# 32nbIoT-1_2.net
KiCad netlist of a schematic drawn in EAGLE
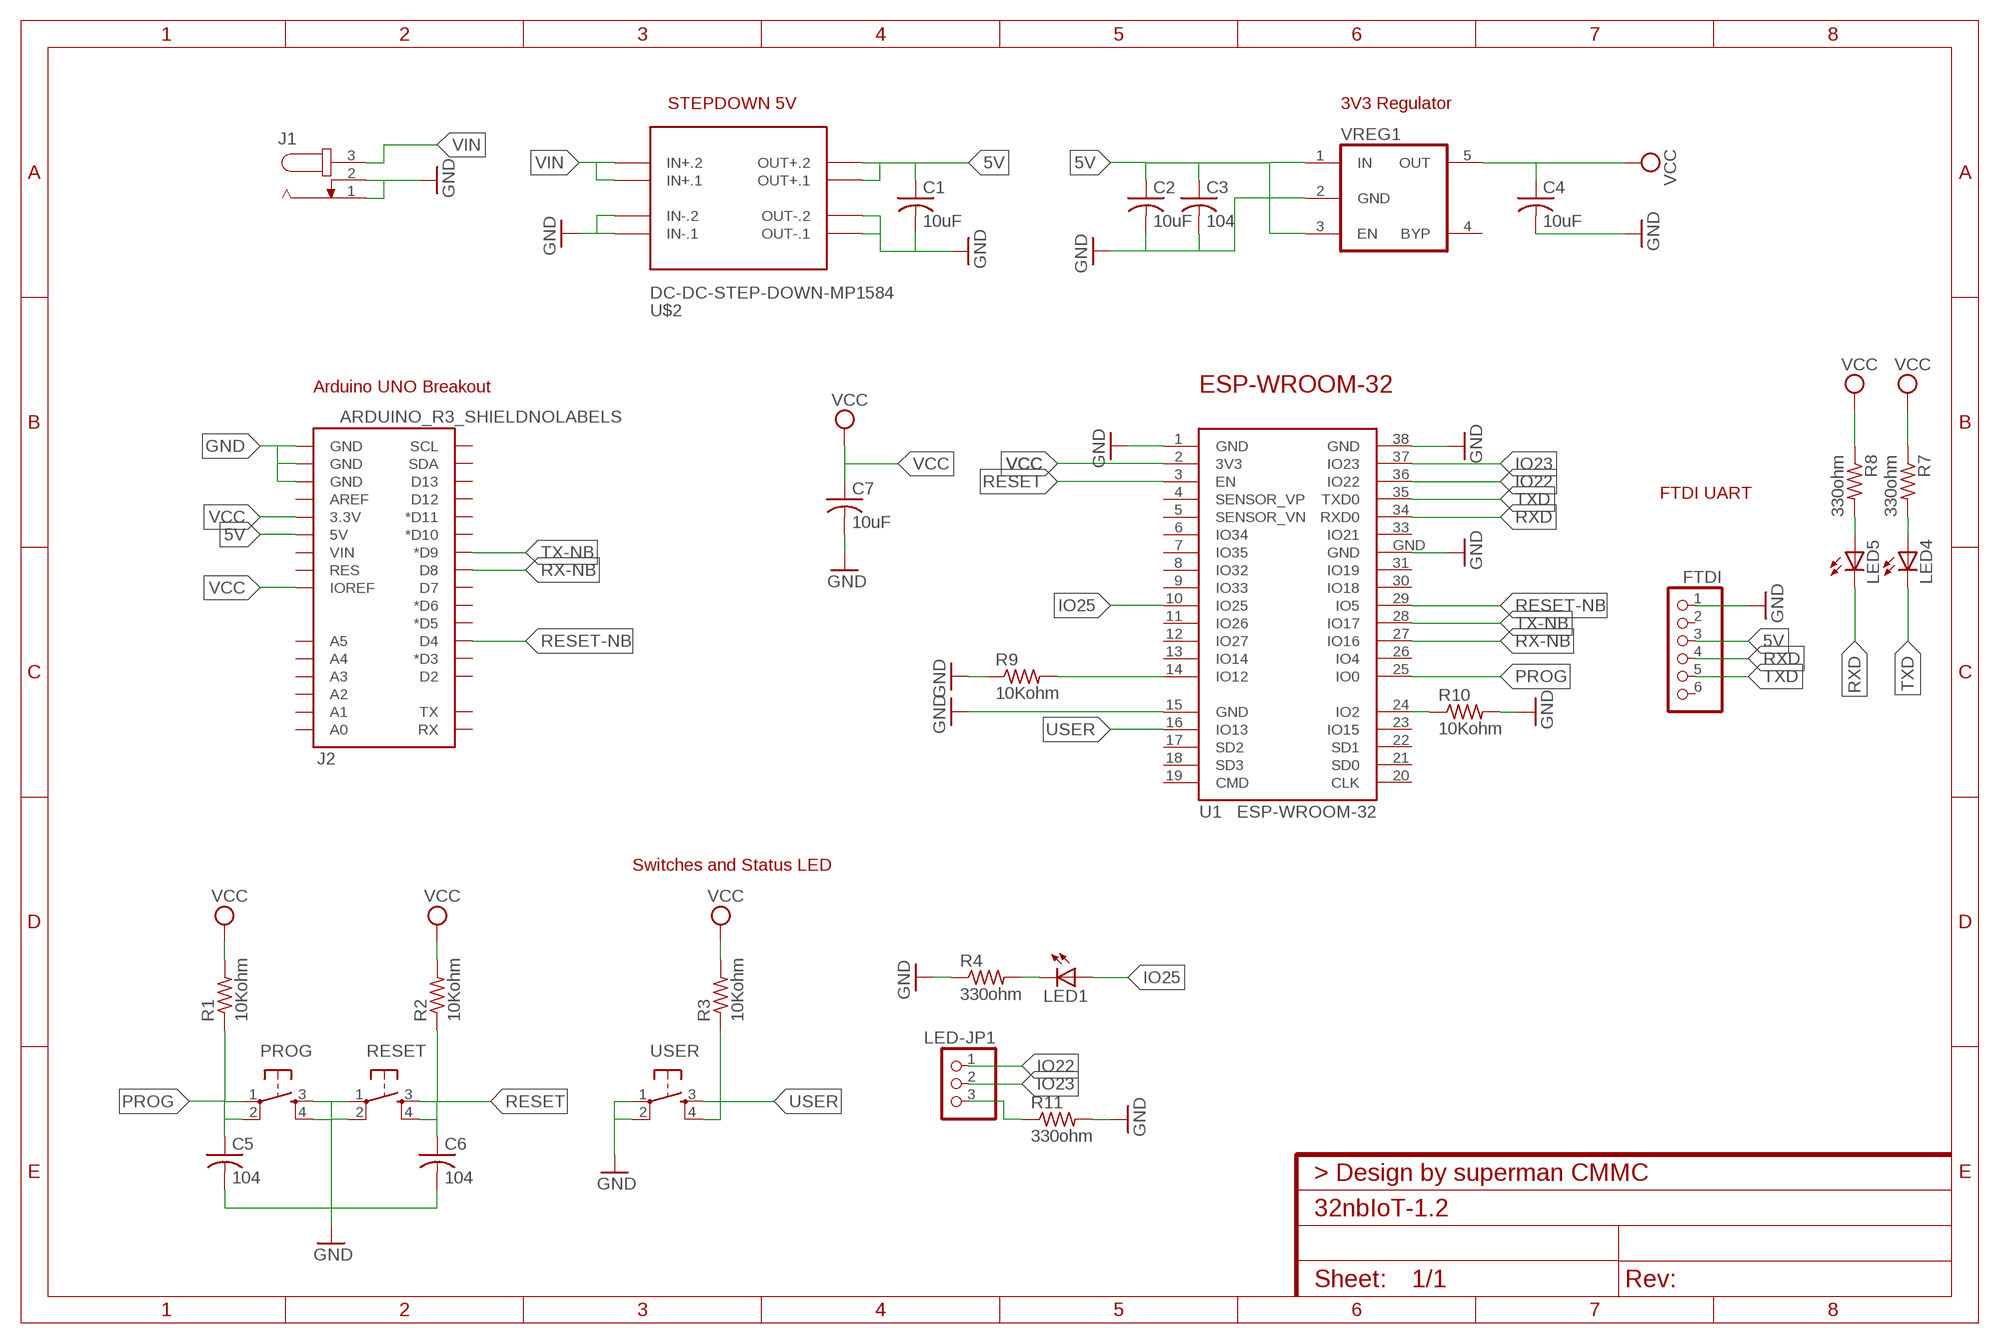
[diagram p0: schematic, sheet 1]

(export (version "E")
  (design (tool "Eeschema 10.0.6"))
  (components
    (comp (ref "C1")
      (value "10uF")
      (footprint "eagle-import:C0805")
      (libsource (lib "eagle-import") (part "C-USC0805"))
    )
    (comp (ref "C2")
      (value "10uF")
      (footprint "eagle-import:C0805")
      (libsource (lib "eagle-import") (part "C-USC0805"))
    )
    (comp (ref "C3")
      (value "104")
      (footprint "eagle-import:C0805")
      (libsource (lib "eagle-import") (part "C-USC0805"))
    )
    (comp (ref "C4")
      (value "10uF")
      (footprint "eagle-import:C0805")
      (libsource (lib "eagle-import") (part "C-USC0805"))
    )
    (comp (ref "C5")
      (value "104")
      (footprint "eagle-import:C0805")
      (libsource (lib "eagle-import") (part "C-USC0805"))
    )
    (comp (ref "C6")
      (value "104")
      (footprint "eagle-import:C0805")
      (libsource (lib "eagle-import") (part "C-USC0805"))
    )
    (comp (ref "C7")
      (value "10uF")
      (footprint "eagle-import:C0805")
      (libsource (lib "eagle-import") (part "C-USC0805"))
    )
    (comp (ref "FTDI")
      (value "PINHD-1X6")
      (footprint "eagle-import:1X06")
      (libsource (lib "eagle-import") (part "PINHD-1X6"))
    )
    (comp (ref "J1")
      (value "JACK-PLUG1")
      (footprint "eagle-import:SPC4078")
      (libsource (lib "eagle-import") (part "JACK-PLUG1"))
    )
    (comp (ref "J2")
      (value "ARDUINO_R3_SHIELDNOLABELS")
      (footprint "eagle-import:UNO_R3_SHIELD_NOLABELS")
      (libsource (lib "eagle-import") (part "ARDUINO_R3_SHIELDNOLABELS"))
    )
    (comp (ref "LED-JP1")
      (value "PINHD-1X3/90")
      (footprint "eagle-import:1X03_90")
      (libsource (lib "eagle-import") (part "PINHD-1X3/90"))
    )
    (comp (ref "LED1")
      (value "LEDCHIPLED_0805")
      (footprint "eagle-import:CHIPLED_0805")
      (libsource (lib "eagle-import") (part "LEDCHIPLED_0805"))
    )
    (comp (ref "LED4")
      (value "LEDCHIPLED_0805")
      (footprint "eagle-import:CHIPLED_0805")
      (libsource (lib "eagle-import") (part "LEDCHIPLED_0805"))
    )
    (comp (ref "LED5")
      (value "LEDCHIPLED_0805")
      (footprint "eagle-import:CHIPLED_0805")
      (libsource (lib "eagle-import") (part "LEDCHIPLED_0805"))
    )
    (comp (ref "PROG")
      (value "TAC_SWITCHPTH")
      (footprint "eagle-import:TACTILE-PTH")
      (libsource (lib "eagle-import") (part "TAC_SWITCHPTH"))
    )
    (comp (ref "R1")
      (value "10Kohm")
      (footprint "eagle-import:R0805W")
      (libsource (lib "eagle-import") (part "R-US_R0805W"))
    )
    (comp (ref "R2")
      (value "10Kohm")
      (footprint "eagle-import:R0805W")
      (libsource (lib "eagle-import") (part "R-US_R0805W"))
    )
    (comp (ref "R3")
      (value "10Kohm")
      (footprint "eagle-import:R0805W")
      (libsource (lib "eagle-import") (part "R-US_R0805W"))
    )
    (comp (ref "R4")
      (value "330ohm")
      (footprint "eagle-import:R0805W")
      (libsource (lib "eagle-import") (part "R-US_R0805W"))
    )
    (comp (ref "R7")
      (value "330ohm")
      (footprint "eagle-import:R0805W")
      (libsource (lib "eagle-import") (part "R-US_R0805W"))
    )
    (comp (ref "R8")
      (value "330ohm")
      (footprint "eagle-import:R0805W")
      (libsource (lib "eagle-import") (part "R-US_R0805W"))
    )
    (comp (ref "R9")
      (value "10Kohm")
      (footprint "eagle-import:R0805W")
      (libsource (lib "eagle-import") (part "R-US_R0805W"))
    )
    (comp (ref "R10")
      (value "10Kohm")
      (footprint "eagle-import:R0805W")
      (libsource (lib "eagle-import") (part "R-US_R0805W"))
    )
    (comp (ref "R11")
      (value "330ohm")
      (footprint "eagle-import:R0805W")
      (libsource (lib "eagle-import") (part "R-US_R0805W"))
    )
    (comp (ref "RESET")
      (value "TAC_SWITCHPTH")
      (footprint "eagle-import:TACTILE-PTH")
      (libsource (lib "eagle-import") (part "TAC_SWITCHPTH"))
    )
    (comp (ref "U$2")
      (value "DC-DC-STEP-DOWN-MP1584")
      (footprint "eagle-import:DC-DC-STEP-DOWN-MP1584")
      (libsource (lib "eagle-import") (part "DC-DC-STEP-DOWN-MP1584"))
    )
    (comp (ref "U1")
      (value "ESP-WROOM-32")
      (footprint "eagle-import:ESP-WROOM-32")
      (libsource (lib "eagle-import") (part "ESP-WROOM-32"))
    )
    (comp (ref "USER")
      (value "TAC_SWITCHPTH")
      (footprint "eagle-import:TACTILE-PTH")
      (libsource (lib "eagle-import") (part "TAC_SWITCHPTH"))
    )
    (comp (ref "VREG1")
      (value "VREG_5PINS-SOT-23-5")
      (footprint "eagle-import:SOT-23-5")
      (libsource (lib "eagle-import") (part "VREG_5PINS-SOT-23-5"))
    )
  )
  (nets
    (net (code "1") (name "5V") (class "Default")
      (node (ref "C1") (pin "1") (pinfunction "1_1") (pintype "passive"))
      (node (ref "C2") (pin "1") (pinfunction "1_1") (pintype "passive"))
      (node (ref "C3") (pin "1") (pinfunction "1_1") (pintype "passive"))
      (node (ref "FTDI") (pin "3") (pinfunction "3_3") (pintype "passive"))
      (node (ref "J2") (pin "5V") (pinfunction "5V_5V") (pintype "bidirectional"))
      (node (ref "U$2") (pin "OUT+.1") (pinfunction "OUT+.1_OUT+.1") (pintype "bidirectional"))
      (node (ref "U$2") (pin "OUT+.2") (pinfunction "OUT+.2_OUT+.2") (pintype "bidirectional"))
      (node (ref "VREG1") (pin "1") (pinfunction "IN_1") (pintype "bidirectional"))
      (node (ref "VREG1") (pin "3") (pinfunction "EN_3") (pintype "bidirectional"))
    )
    (net (code "2") (name "GND") (class "Default")
      (node (ref "C1") (pin "2") (pinfunction "2_2") (pintype "passive"))
      (node (ref "C2") (pin "2") (pinfunction "2_2") (pintype "passive"))
      (node (ref "C3") (pin "2") (pinfunction "2_2") (pintype "passive"))
      (node (ref "C4") (pin "2") (pinfunction "2_2") (pintype "passive"))
      (node (ref "C5") (pin "2") (pinfunction "2_2") (pintype "passive"))
      (node (ref "C6") (pin "2") (pinfunction "2_2") (pintype "passive"))
      (node (ref "C7") (pin "2") (pinfunction "2_2") (pintype "passive"))
      (node (ref "FTDI") (pin "1") (pinfunction "1_1") (pintype "passive"))
      (node (ref "J1") (pin "1") (pinfunction "1_1") (pintype "passive"))
      (node (ref "J1") (pin "2") (pinfunction "2_2") (pintype "passive"))
      (node (ref "J2") (pin "GND@0") (pinfunction "GND_GND@0") (pintype "bidirectional"))
      (node (ref "J2") (pin "GND@1") (pinfunction "GND_GND@1") (pintype "bidirectional"))
      (node (ref "J2") (pin "GND@2") (pinfunction "GND_GND@2") (pintype "bidirectional"))
      (node (ref "PROG") (pin "3") (pinfunction "3_3") (pintype "passive"))
      (node (ref "PROG") (pin "4") (pinfunction "4_4") (pintype "passive"))
      (node (ref "R10") (pin "2") (pinfunction "2_2") (pintype "passive"))
      (node (ref "R11") (pin "2") (pinfunction "2_2") (pintype "passive"))
      (node (ref "R4") (pin "1") (pinfunction "1_1") (pintype "passive"))
      (node (ref "R9") (pin "1") (pinfunction "1_1") (pintype "passive"))
      (node (ref "RESET") (pin "1") (pinfunction "1_1") (pintype "passive"))
      (node (ref "RESET") (pin "2") (pinfunction "2_2") (pintype "passive"))
      (node (ref "U$2") (pin "IN-.1") (pinfunction "IN-.1_IN-.1") (pintype "bidirectional"))
      (node (ref "U$2") (pin "IN-.2") (pinfunction "IN-.2_IN-.2") (pintype "bidirectional"))
      (node (ref "U$2") (pin "OUT-.1") (pinfunction "OUT-.1_OUT-.1") (pintype "bidirectional"))
      (node (ref "U$2") (pin "OUT-.2") (pinfunction "OUT-.2_OUT-.2") (pintype "bidirectional"))
      (node (ref "U1") (pin "1") (pinfunction "GND_1") (pintype "power_in"))
      (node (ref "U1") (pin "15") (pinfunction "GND_15") (pintype "power_in"))
      (node (ref "U1") (pin "38") (pinfunction "GND_38") (pintype "power_in"))
      (node (ref "U1") (pin "GND") (pinfunction "GND_GND") (pintype "power_in"))
      (node (ref "USER") (pin "1") (pinfunction "1_1") (pintype "passive"))
      (node (ref "USER") (pin "2") (pinfunction "2_2") (pintype "passive"))
      (node (ref "VREG1") (pin "2") (pinfunction "GND_2") (pintype "bidirectional"))
    )
    (net (code "3") (name "IO22") (class "Default")
      (node (ref "LED-JP1") (pin "1") (pinfunction "1_1") (pintype "passive"))
      (node (ref "U1") (pin "36") (pinfunction "IO22_36") (pintype "bidirectional"))
    )
    (net (code "4") (name "IO23") (class "Default")
      (node (ref "LED-JP1") (pin "2") (pinfunction "2_2") (pintype "passive"))
      (node (ref "U1") (pin "37") (pinfunction "IO23_37") (pintype "bidirectional"))
    )
    (net (code "5") (name "IO25") (class "Default")
      (node (ref "LED1") (pin "A") (pinfunction "A_A") (pintype "passive"))
      (node (ref "U1") (pin "10") (pinfunction "IO25_10") (pintype "bidirectional"))
    )
    (net (code "6") (name "Net-(LED-JP1-Pad3)") (class "Default")
      (node (ref "LED-JP1") (pin "3") (pinfunction "3_3") (pintype "passive"))
      (node (ref "R11") (pin "1") (pinfunction "1_1") (pintype "passive"))
    )
    (net (code "7") (name "Net-(LED1-PadC)") (class "Default")
      (node (ref "LED1") (pin "C") (pinfunction "C_C") (pintype "passive"))
      (node (ref "R4") (pin "2") (pinfunction "2_2") (pintype "passive"))
    )
    (net (code "8") (name "Net-(LED4-PadA)") (class "Default")
      (node (ref "LED4") (pin "A") (pinfunction "A_A") (pintype "passive"))
      (node (ref "R7") (pin "2") (pinfunction "2_2") (pintype "passive"))
    )
    (net (code "9") (name "Net-(LED5-PadA)") (class "Default")
      (node (ref "LED5") (pin "A") (pinfunction "A_A") (pintype "passive"))
      (node (ref "R8") (pin "2") (pinfunction "2_2") (pintype "passive"))
    )
    (net (code "10") (name "Net-(U1-IO2)") (class "Default")
      (node (ref "R10") (pin "1") (pinfunction "1_1") (pintype "passive"))
      (node (ref "U1") (pin "24") (pinfunction "IO2_24") (pintype "bidirectional"))
    )
    (net (code "11") (name "Net-(U1-IO12)") (class "Default")
      (node (ref "R9") (pin "2") (pinfunction "2_2") (pintype "passive"))
      (node (ref "U1") (pin "14") (pinfunction "IO12_14") (pintype "bidirectional"))
    )
    (net (code "12") (name "PROG") (class "Default")
      (node (ref "C5") (pin "1") (pinfunction "1_1") (pintype "passive"))
      (node (ref "PROG") (pin "1") (pinfunction "1_1") (pintype "passive"))
      (node (ref "PROG") (pin "2") (pinfunction "2_2") (pintype "passive"))
      (node (ref "R1") (pin "1") (pinfunction "1_1") (pintype "passive"))
      (node (ref "U1") (pin "25") (pinfunction "IO0_25") (pintype "bidirectional"))
    )
    (net (code "13") (name "RESET") (class "Default")
      (node (ref "C6") (pin "1") (pinfunction "1_1") (pintype "passive"))
      (node (ref "R2") (pin "1") (pinfunction "1_1") (pintype "passive"))
      (node (ref "RESET") (pin "3") (pinfunction "3_3") (pintype "passive"))
      (node (ref "RESET") (pin "4") (pinfunction "4_4") (pintype "passive"))
      (node (ref "U1") (pin "3") (pinfunction "EN_3") (pintype "input"))
    )
    (net (code "14") (name "RESET-NB") (class "Default")
      (node (ref "J2") (pin "D4") (pinfunction "D4_D4") (pintype "bidirectional"))
      (node (ref "U1") (pin "29") (pinfunction "IO5_29") (pintype "bidirectional"))
    )
    (net (code "15") (name "RX-NB") (class "Default")
      (node (ref "J2") (pin "D8") (pinfunction "D8_D8") (pintype "bidirectional"))
      (node (ref "U1") (pin "27") (pinfunction "IO16_27") (pintype "bidirectional"))
    )
    (net (code "16") (name "RXD") (class "Default")
      (node (ref "FTDI") (pin "4") (pinfunction "4_4") (pintype "passive"))
      (node (ref "LED5") (pin "C") (pinfunction "C_C") (pintype "passive"))
      (node (ref "U1") (pin "34") (pinfunction "RXD0_34") (pintype "bidirectional"))
    )
    (net (code "17") (name "TX-NB") (class "Default")
      (node (ref "J2") (pin "D9") (pinfunction "*D9_D9") (pintype "bidirectional"))
      (node (ref "U1") (pin "28") (pinfunction "IO17_28") (pintype "bidirectional"))
    )
    (net (code "18") (name "TXD") (class "Default")
      (node (ref "FTDI") (pin "5") (pinfunction "5_5") (pintype "passive"))
      (node (ref "LED4") (pin "C") (pinfunction "C_C") (pintype "passive"))
      (node (ref "U1") (pin "35") (pinfunction "TXD0_35") (pintype "bidirectional"))
    )
    (net (code "19") (name "USER") (class "Default")
      (node (ref "R3") (pin "1") (pinfunction "1_1") (pintype "passive"))
      (node (ref "U1") (pin "16") (pinfunction "IO13_16") (pintype "bidirectional"))
      (node (ref "USER") (pin "3") (pinfunction "3_3") (pintype "passive"))
      (node (ref "USER") (pin "4") (pinfunction "4_4") (pintype "passive"))
    )
    (net (code "20") (name "VCC") (class "Default")
      (node (ref "C4") (pin "1") (pinfunction "1_1") (pintype "passive"))
      (node (ref "C7") (pin "1") (pinfunction "1_1") (pintype "passive"))
      (node (ref "J2") (pin "3.3V") (pinfunction "3.3V_3.3V") (pintype "bidirectional"))
      (node (ref "J2") (pin "IOREF") (pinfunction "IOREF_IOREF") (pintype "bidirectional"))
      (node (ref "R1") (pin "2") (pinfunction "2_2") (pintype "passive"))
      (node (ref "R2") (pin "2") (pinfunction "2_2") (pintype "passive"))
      (node (ref "R3") (pin "2") (pinfunction "2_2") (pintype "passive"))
      (node (ref "R7") (pin "1") (pinfunction "1_1") (pintype "passive"))
      (node (ref "R8") (pin "1") (pinfunction "1_1") (pintype "passive"))
      (node (ref "U1") (pin "2") (pinfunction "3V3_2") (pintype "power_in"))
      (node (ref "VREG1") (pin "5") (pinfunction "OUT_5") (pintype "bidirectional"))
    )
    (net (code "21") (name "VIN") (class "Default")
      (node (ref "J1") (pin "3") (pinfunction "3_3") (pintype "passive"))
      (node (ref "U$2") (pin "IN+.1") (pinfunction "IN+.1_IN+.1") (pintype "bidirectional"))
      (node (ref "U$2") (pin "IN+.2") (pinfunction "IN+.2_IN+.2") (pintype "bidirectional"))
    )
    (net (code "22") (name "unconnected-(FTDI-Pad2)") (class "Default")
      (node (ref "FTDI") (pin "2") (pinfunction "2_2") (pintype "passive"))
    )
    (net (code "23") (name "unconnected-(FTDI-Pad6)") (class "Default")
      (node (ref "FTDI") (pin "6") (pinfunction "6_6") (pintype "passive"))
    )
    (net (code "24") (name "unconnected-(J2-*D3-PadD3)") (class "Default")
      (node (ref "J2") (pin "D3") (pinfunction "*D3_D3") (pintype "bidirectional"))
    )
    (net (code "25") (name "unconnected-(J2-*D5-PadD5)") (class "Default")
      (node (ref "J2") (pin "D5") (pinfunction "*D5_D5") (pintype "bidirectional"))
    )
    (net (code "26") (name "unconnected-(J2-*D6-PadD6)") (class "Default")
      (node (ref "J2") (pin "D6") (pinfunction "*D6_D6") (pintype "bidirectional"))
    )
    (net (code "27") (name "unconnected-(J2-*D10-PadD10)") (class "Default")
      (node (ref "J2") (pin "D10") (pinfunction "*D10_D10") (pintype "bidirectional"))
    )
    (net (code "28") (name "unconnected-(J2-*D11-PadD11)") (class "Default")
      (node (ref "J2") (pin "D11") (pinfunction "*D11_D11") (pintype "bidirectional"))
    )
    (net (code "29") (name "unconnected-(J2-PadA0)") (class "Default")
      (node (ref "J2") (pin "A0") (pinfunction "A0_A0") (pintype "bidirectional"))
    )
    (net (code "30") (name "unconnected-(J2-PadA1)") (class "Default")
      (node (ref "J2") (pin "A1") (pinfunction "A1_A1") (pintype "bidirectional"))
    )
    (net (code "31") (name "unconnected-(J2-PadA2)") (class "Default")
      (node (ref "J2") (pin "A2") (pinfunction "A2_A2") (pintype "bidirectional"))
    )
    (net (code "32") (name "unconnected-(J2-PadA3)") (class "Default")
      (node (ref "J2") (pin "A3") (pinfunction "A3_A3") (pintype "bidirectional"))
    )
    (net (code "33") (name "unconnected-(J2-PadA4)") (class "Default")
      (node (ref "J2") (pin "A4") (pinfunction "A4_A4") (pintype "bidirectional"))
    )
    (net (code "34") (name "unconnected-(J2-PadA5)") (class "Default")
      (node (ref "J2") (pin "A5") (pinfunction "A5_A5") (pintype "bidirectional"))
    )
    (net (code "35") (name "unconnected-(J2-PadAREF)") (class "Default")
      (node (ref "J2") (pin "AREF") (pinfunction "AREF_AREF") (pintype "bidirectional"))
    )
    (net (code "36") (name "unconnected-(J2-PadD2)") (class "Default")
      (node (ref "J2") (pin "D2") (pinfunction "D2_D2") (pintype "bidirectional"))
    )
    (net (code "37") (name "unconnected-(J2-PadD7)") (class "Default")
      (node (ref "J2") (pin "D7") (pinfunction "D7_D7") (pintype "bidirectional"))
    )
    (net (code "38") (name "unconnected-(J2-PadD12)") (class "Default")
      (node (ref "J2") (pin "D12") (pinfunction "D12_D12") (pintype "bidirectional"))
    )
    (net (code "39") (name "unconnected-(J2-PadD13)") (class "Default")
      (node (ref "J2") (pin "D13") (pinfunction "D13_D13") (pintype "bidirectional"))
    )
    (net (code "40") (name "unconnected-(J2-PadRES)") (class "Default")
      (node (ref "J2") (pin "RES") (pinfunction "RES_RES") (pintype "bidirectional"))
    )
    (net (code "41") (name "unconnected-(J2-PadRX)") (class "Default")
      (node (ref "J2") (pin "RX") (pinfunction "RX_RX") (pintype "bidirectional"))
    )
    (net (code "42") (name "unconnected-(J2-PadSCL)") (class "Default")
      (node (ref "J2") (pin "SCL") (pinfunction "SCL_SCL") (pintype "bidirectional"))
    )
    (net (code "43") (name "unconnected-(J2-PadSDA)") (class "Default")
      (node (ref "J2") (pin "SDA") (pinfunction "SDA_SDA") (pintype "bidirectional"))
    )
    (net (code "44") (name "unconnected-(J2-PadTX)") (class "Default")
      (node (ref "J2") (pin "TX") (pinfunction "TX_TX") (pintype "bidirectional"))
    )
    (net (code "45") (name "unconnected-(J2-PadVIN)") (class "Default")
      (node (ref "J2") (pin "VIN") (pinfunction "VIN_VIN") (pintype "bidirectional"))
    )
    (net (code "46") (name "unconnected-(U1-CLK-Pad20)") (class "Default")
      (node (ref "U1") (pin "20") (pinfunction "CLK_20") (pintype "bidirectional"))
    )
    (net (code "47") (name "unconnected-(U1-CMD-Pad19)") (class "Default")
      (node (ref "U1") (pin "19") (pinfunction "CMD_19") (pintype "bidirectional"))
    )
    (net (code "48") (name "unconnected-(U1-IO4-Pad26)") (class "Default")
      (node (ref "U1") (pin "26") (pinfunction "IO4_26") (pintype "bidirectional"))
    )
    (net (code "49") (name "unconnected-(U1-IO14-Pad13)") (class "Default")
      (node (ref "U1") (pin "13") (pinfunction "IO14_13") (pintype "bidirectional"))
    )
    (net (code "50") (name "unconnected-(U1-IO15-Pad23)") (class "Default")
      (node (ref "U1") (pin "23") (pinfunction "IO15_23") (pintype "bidirectional"))
    )
    (net (code "51") (name "unconnected-(U1-IO18-Pad30)") (class "Default")
      (node (ref "U1") (pin "30") (pinfunction "IO18_30") (pintype "bidirectional"))
    )
    (net (code "52") (name "unconnected-(U1-IO19-Pad31)") (class "Default")
      (node (ref "U1") (pin "31") (pinfunction "IO19_31") (pintype "bidirectional"))
    )
    (net (code "53") (name "unconnected-(U1-IO21-Pad33)") (class "Default")
      (node (ref "U1") (pin "33") (pinfunction "IO21_33") (pintype "bidirectional"))
    )
    (net (code "54") (name "unconnected-(U1-IO26-Pad11)") (class "Default")
      (node (ref "U1") (pin "11") (pinfunction "IO26_11") (pintype "bidirectional"))
    )
    (net (code "55") (name "unconnected-(U1-IO27-Pad12)") (class "Default")
      (node (ref "U1") (pin "12") (pinfunction "IO27_12") (pintype "bidirectional"))
    )
    (net (code "56") (name "unconnected-(U1-IO32-Pad8)") (class "Default")
      (node (ref "U1") (pin "8") (pinfunction "IO32_8") (pintype "bidirectional"))
    )
    (net (code "57") (name "unconnected-(U1-IO33-Pad9)") (class "Default")
      (node (ref "U1") (pin "9") (pinfunction "IO33_9") (pintype "bidirectional"))
    )
    (net (code "58") (name "unconnected-(U1-IO34-Pad6)") (class "Default")
      (node (ref "U1") (pin "6") (pinfunction "IO34_6") (pintype "bidirectional"))
    )
    (net (code "59") (name "unconnected-(U1-IO35-Pad7)") (class "Default")
      (node (ref "U1") (pin "7") (pinfunction "IO35_7") (pintype "bidirectional"))
    )
    (net (code "60") (name "unconnected-(U1-SD0-Pad21)") (class "Default")
      (node (ref "U1") (pin "21") (pinfunction "SD0_21") (pintype "bidirectional"))
    )
    (net (code "61") (name "unconnected-(U1-SD1-Pad22)") (class "Default")
      (node (ref "U1") (pin "22") (pinfunction "SD1_22") (pintype "bidirectional"))
    )
    (net (code "62") (name "unconnected-(U1-SD2-Pad17)") (class "Default")
      (node (ref "U1") (pin "17") (pinfunction "SD2_17") (pintype "bidirectional"))
    )
    (net (code "63") (name "unconnected-(U1-SD3-Pad18)") (class "Default")
      (node (ref "U1") (pin "18") (pinfunction "SD3_18") (pintype "bidirectional"))
    )
    (net (code "64") (name "unconnected-(U1-SENSOR_VN-Pad5)") (class "Default")
      (node (ref "U1") (pin "5") (pinfunction "SENSOR_VN_5") (pintype "bidirectional"))
    )
    (net (code "65") (name "unconnected-(U1-SENSOR_VP-Pad4)") (class "Default")
      (node (ref "U1") (pin "4") (pinfunction "SENSOR_VP_4") (pintype "bidirectional"))
    )
    (net (code "66") (name "unconnected-(VREG1-BYP-Pad4)") (class "Default")
      (node (ref "VREG1") (pin "4") (pinfunction "BYP_4") (pintype "bidirectional"))
    )
  )
)
